# ipmi.net
KiCad netlist of a schematic drawn in Altium Designer
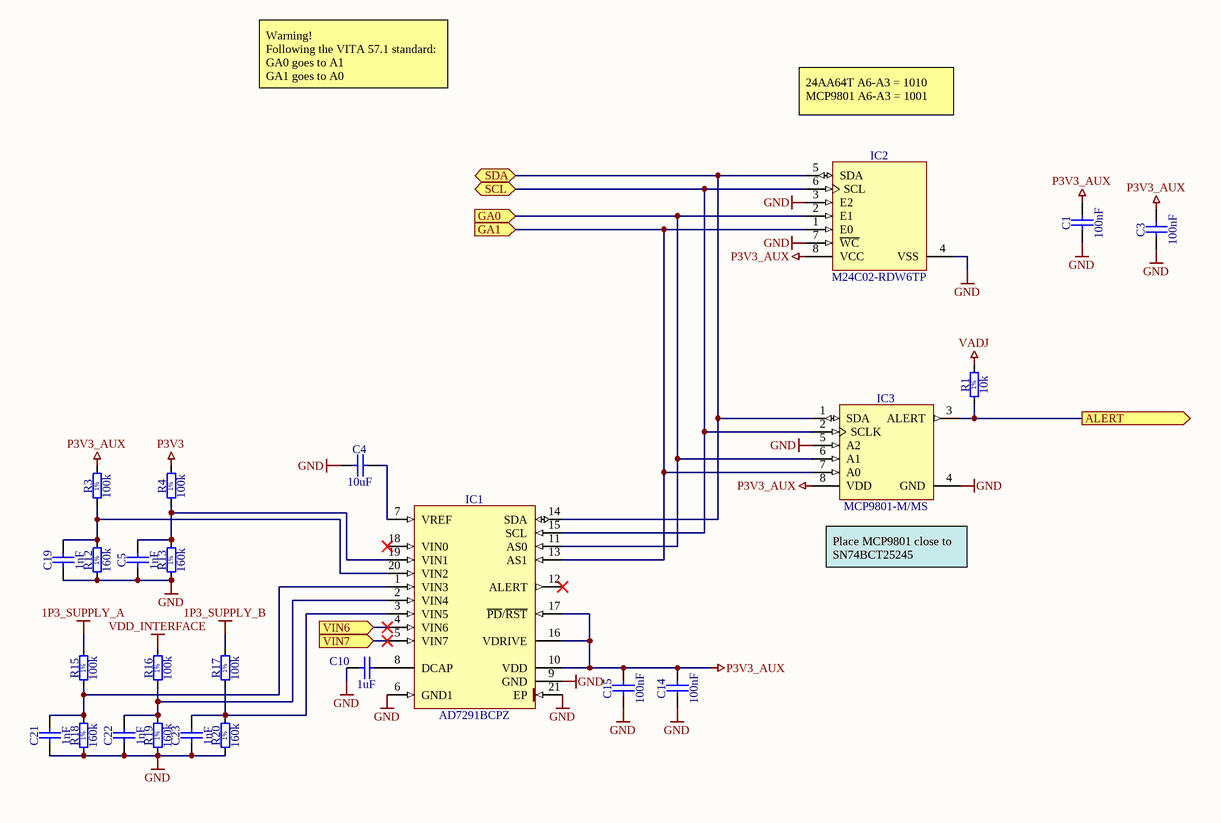
[diagram p0: ipmi.SchDoc]

(export (version "E")
  (design (tool "Eeschema 10.0.6"))
  (components
    (comp (ref "C1")
      (value "100nF")
      (footprint "CAPC1005X55N")
      (description "Non-polarised capacitor")
      (fields
        (field (name "PART NUMBER") "CC0402_100NF_16V_10%_X7R")
        (field (name "VOLTAGE") "16V")
        (field (name "AUTHOR") "CERN DEM JLC")
      )
      (libsource (lib "Capacitors") (part "Capacitor - non polarized"))
    )
    (comp (ref "C3")
      (value "100nF")
      (footprint "CAPC1005X55N")
      (description "Non-polarised capacitor")
      (fields
        (field (name "PART NUMBER") "CC0402_100NF_16V_10%_X7R")
        (field (name "VOLTAGE") "16V")
        (field (name "AUTHOR") "CERN DEM JLC")
      )
      (libsource (lib "Capacitors") (part "Capacitor - non polarized"))
    )
    (comp (ref "C4")
      (value "10uF")
      (footprint "CAPC1608X87N")
      (description "Non-polarised capacitor")
      (fields
        (field (name "PART NUMBER") "CC0603_10UF_6.3V_20%_X5R")
        (field (name "VOLTAGE") "6.3V")
        (field (name "AUTHOR") "CERN DEM JLC")
      )
      (libsource (lib "Capacitors") (part "Capacitor - non polarized"))
    )
    (comp (ref "C5")
      (value "1nF")
      (footprint "CAPC1005X55N")
      (description "Non-polarised capacitor")
      (fields
        (field (name "PART NUMBER") "CC0402_1NF_50V_10%_X7R")
        (field (name "VOLTAGE") "50V")
        (field (name "AUTHOR") "CERN DEM JLC")
      )
      (libsource (lib "Capacitors") (part "Capacitor - non polarized"))
    )
    (comp (ref "C10")
      (value "1uF")
      (footprint "CAPC1608X87N")
      (description "Non-polarised capacitor")
      (fields
        (field (name "PART NUMBER") "CC0603_1UF_16V_10%_X7R")
        (field (name "VOLTAGE") "16V")
        (field (name "AUTHOR") "CERN DEM JLC")
      )
      (libsource (lib "Capacitors") (part "Capacitor - non polarized"))
    )
    (comp (ref "C14")
      (value "100nF")
      (footprint "CAPC1005X55N")
      (description "Non-polarised capacitor")
      (fields
        (field (name "PART NUMBER") "CC0402_100NF_16V_10%_X7R")
        (field (name "VOLTAGE") "16V")
        (field (name "AUTHOR") "CERN DEM JLC")
      )
      (libsource (lib "Capacitors") (part "Capacitor - non polarized"))
    )
    (comp (ref "C15")
      (value "100nF")
      (footprint "CAPC1005X55N")
      (description "Non-polarised capacitor")
      (fields
        (field (name "PART NUMBER") "CC0402_100NF_16V_10%_X7R")
        (field (name "VOLTAGE") "16V")
        (field (name "AUTHOR") "CERN DEM JLC")
      )
      (libsource (lib "Capacitors") (part "Capacitor - non polarized"))
    )
    (comp (ref "C19")
      (value "1nF")
      (footprint "CAPC1005X55N")
      (description "Non-polarised capacitor")
      (fields
        (field (name "PART NUMBER") "CC0402_1NF_50V_10%_X7R")
        (field (name "VOLTAGE") "50V")
        (field (name "AUTHOR") "CERN DEM JLC")
      )
      (libsource (lib "Capacitors") (part "Capacitor - non polarized"))
    )
    (comp (ref "C21")
      (value "1nF")
      (footprint "CAPC1005X55N")
      (description "Non-polarised capacitor")
      (fields
        (field (name "PART NUMBER") "CC0402_1NF_50V_10%_X7R")
        (field (name "VOLTAGE") "50V")
        (field (name "AUTHOR") "CERN DEM JLC")
      )
      (libsource (lib "Capacitors") (part "Capacitor - non polarized"))
    )
    (comp (ref "C22")
      (value "1nF")
      (footprint "CAPC1005X55N")
      (description "Non-polarised capacitor")
      (fields
        (field (name "PART NUMBER") "CC0402_1NF_50V_10%_X7R")
        (field (name "VOLTAGE") "50V")
        (field (name "AUTHOR") "CERN DEM JLC")
      )
      (libsource (lib "Capacitors") (part "Capacitor - non polarized"))
    )
    (comp (ref "C23")
      (value "1nF")
      (footprint "CAPC1005X55N")
      (description "Non-polarised capacitor")
      (fields
        (field (name "PART NUMBER") "CC0402_1NF_50V_10%_X7R")
        (field (name "VOLTAGE") "50V")
        (field (name "AUTHOR") "CERN DEM JLC")
      )
      (libsource (lib "Capacitors") (part "Capacitor - non polarized"))
    )
    (comp (ref "IC1")
      (value "AD7291BCPZ")
      (footprint "QFN50P400X400X80-21N-S275")
      (description "8-Channel, I2C, 12-Bit SAR ADC with Temperature Sensor")
      (fields (field (name "MANUFACTURER") "ANALOG DEVICES") (field (name "AUTHOR") "CERN DEM JLC"))
      (libsource (lib "ICs And Semiconductors") (part "AD7291"))
    )
    (comp (ref "IC2")
      (value "M24C02-RDW6TP")
      (footprint "SOP65P640X120-8N")
      (description "2-Kbit (256 x 8bit) Serial I2C Bus EEPROM")
      (fields (field (name "MANUFACTURER") "ST MICROELECTRONICS") (field (name "AUTHOR") "CERN DEM JLC"))
      (libsource (lib "ICs And Semiconductors") (part "M24C02‐RDW"))
    )
    (comp (ref "IC3")
      (value "MCP9801-M/MS")
      (footprint "SOP65P490X110-8N")
      (description "2-Wire High-Accuracy Temperature Sensor")
      (fields (field (name "MANUFACTURER") "MICROCHIP TECHNOLOGIY") (field (name "AUTHOR") "CERN DEM JLC"))
      (libsource (lib "ICs And Semiconductors") (part "MCP9801-M/MS"))
    )
    (comp (ref "R1")
      (value "10k")
      (footprint "RESC1005X40N")
      (description "Resistor - 1%")
      (fields
        (field (name "PART NUMBER") "R0402_10K_1%_0.0625W_100PPM")
        (field (name "POWER") "0.0625W")
        (field (name "AUTHOR") "CERN DEM JLC")
      )
      (libsource (lib "Resistors") (part "Resistor - 1%"))
    )
    (comp (ref "R3")
      (value "100k")
      (footprint "RESC1005X40N")
      (description "Resistor - 1%")
      (fields
        (field (name "PART NUMBER") "R0402_100K_1%_0.0625W_100PPM")
        (field (name "POWER") "0.0625W")
        (field (name "AUTHOR") "CERN DEM JLC")
      )
      (libsource (lib "Resistors") (part "Resistor - 1%"))
    )
    (comp (ref "R4")
      (value "100k")
      (footprint "RESC1005X40N")
      (description "Resistor - 1%")
      (fields
        (field (name "PART NUMBER") "R0402_100K_1%_0.0625W_100PPM")
        (field (name "POWER") "0.0625W")
        (field (name "AUTHOR") "CERN DEM JLC")
      )
      (libsource (lib "Resistors") (part "Resistor - 1%"))
    )
    (comp (ref "R12")
      (value "160k")
      (footprint "RESC1005X40N")
      (description "Resistor - 1%")
      (fields
        (field (name "PART NUMBER") "R0402_160K_1%_0.0625W_100PPM")
        (field (name "POWER") "0.0625W")
        (field (name "AUTHOR") "CERN DEM JLC")
      )
      (libsource (lib "Resistors") (part "Resistor - 1%"))
    )
    (comp (ref "R13")
      (value "160k")
      (footprint "RESC1005X40N")
      (description "Resistor - 1%")
      (fields
        (field (name "PART NUMBER") "R0402_160K_1%_0.0625W_100PPM")
        (field (name "POWER") "0.0625W")
        (field (name "AUTHOR") "CERN DEM JLC")
      )
      (libsource (lib "Resistors") (part "Resistor - 1%"))
    )
    (comp (ref "R15")
      (value "100k")
      (footprint "RESC1005X40N")
      (description "Resistor - 1%")
      (fields
        (field (name "PART NUMBER") "R0402_100K_1%_0.0625W_100PPM")
        (field (name "POWER") "0.0625W")
        (field (name "AUTHOR") "CERN DEM JLC")
      )
      (libsource (lib "Resistors") (part "Resistor - 1%"))
    )
    (comp (ref "R16")
      (value "100k")
      (footprint "RESC1005X40N")
      (description "Resistor - 1%")
      (fields
        (field (name "PART NUMBER") "R0402_100K_1%_0.0625W_100PPM")
        (field (name "POWER") "0.0625W")
        (field (name "AUTHOR") "CERN DEM JLC")
      )
      (libsource (lib "Resistors") (part "Resistor - 1%"))
    )
    (comp (ref "R17")
      (value "100k")
      (footprint "RESC1005X40N")
      (description "Resistor - 1%")
      (fields
        (field (name "PART NUMBER") "R0402_100K_1%_0.0625W_100PPM")
        (field (name "POWER") "0.0625W")
        (field (name "AUTHOR") "CERN DEM JLC")
      )
      (libsource (lib "Resistors") (part "Resistor - 1%"))
    )
    (comp (ref "R18")
      (value "160k")
      (footprint "RESC1005X40N")
      (description "Resistor - 1%")
      (fields
        (field (name "PART NUMBER") "R0402_160K_1%_0.0625W_100PPM")
        (field (name "POWER") "0.0625W")
        (field (name "AUTHOR") "CERN DEM JLC")
      )
      (libsource (lib "Resistors") (part "Resistor - 1%"))
    )
    (comp (ref "R19")
      (value "160k")
      (footprint "RESC1005X40N")
      (description "Resistor - 1%")
      (fields
        (field (name "PART NUMBER") "R0402_160K_1%_0.0625W_100PPM")
        (field (name "POWER") "0.0625W")
        (field (name "AUTHOR") "CERN DEM JLC")
      )
      (libsource (lib "Resistors") (part "Resistor - 1%"))
    )
    (comp (ref "R20")
      (value "160k")
      (footprint "RESC1005X40N")
      (description "Resistor - 1%")
      (fields
        (field (name "PART NUMBER") "R0402_160K_1%_0.0625W_100PPM")
        (field (name "POWER") "0.0625W")
        (field (name "AUTHOR") "CERN DEM JLC")
      )
      (libsource (lib "Resistors") (part "Resistor - 1%"))
    )
  )
  (nets
    (net (code "1") (name "/ALERT") (class "Default")
      (node (ref "IC3") (pin "3") (pinfunction "ALERT_3") (pintype "output"))
      (node (ref "R1") (pin "1") (pinfunction "1_1") (pintype "passive"))
    )
    (net (code "2") (name "/GA0") (class "Default")
      (node (ref "IC1") (pin "11") (pinfunction "AS0_11") (pintype "input"))
      (node (ref "IC2") (pin "2") (pinfunction "E1_2") (pintype "input"))
      (node (ref "IC3") (pin "6") (pinfunction "A1_6") (pintype "input"))
    )
    (net (code "3") (name "/GA1") (class "Default")
      (node (ref "IC1") (pin "13") (pinfunction "AS1_13") (pintype "input"))
      (node (ref "IC2") (pin "1") (pinfunction "E0_1") (pintype "input"))
      (node (ref "IC3") (pin "7") (pinfunction "A0_7") (pintype "input"))
    )
    (net (code "4") (name "/SCL") (class "Default")
      (node (ref "IC1") (pin "15") (pinfunction "SCL_15") (pintype "input"))
      (node (ref "IC2") (pin "6") (pinfunction "SCL_6") (pintype "input"))
      (node (ref "IC3") (pin "2") (pinfunction "SCLK_2") (pintype "input"))
    )
    (net (code "5") (name "/SDA") (class "Default")
      (node (ref "IC1") (pin "14") (pinfunction "SDA_14") (pintype "bidirectional"))
      (node (ref "IC2") (pin "5") (pinfunction "SDA_5") (pintype "bidirectional"))
      (node (ref "IC3") (pin "1") (pinfunction "SDA_1") (pintype "bidirectional"))
    )
    (net (code "6") (name "/VIN6") (class "Default")
      (node (ref "IC1") (pin "4") (pinfunction "VIN6_4") (pintype "input+no_connect"))
    )
    (net (code "7") (name "/VIN7") (class "Default")
      (node (ref "IC1") (pin "5") (pinfunction "VIN7_5") (pintype "input+no_connect"))
    )
    (net (code "8") (name "1P3_SUPPLY_A") (class "Default")
      (node (ref "R15") (pin "2") (pinfunction "2_2") (pintype "passive"))
    )
    (net (code "9") (name "1P3_SUPPLY_B") (class "Default")
      (node (ref "R17") (pin "2") (pinfunction "2_2") (pintype "passive"))
    )
    (net (code "10") (name "GND") (class "Default")
      (node (ref "C1") (pin "1") (pinfunction "1_1") (pintype "passive"))
      (node (ref "C10") (pin "1") (pinfunction "1_1") (pintype "passive"))
      (node (ref "C14") (pin "1") (pinfunction "1_1") (pintype "passive"))
      (node (ref "C15") (pin "1") (pinfunction "1_1") (pintype "passive"))
      (node (ref "C19") (pin "1") (pinfunction "1_1") (pintype "passive"))
      (node (ref "C21") (pin "1") (pinfunction "1_1") (pintype "passive"))
      (node (ref "C22") (pin "1") (pinfunction "1_1") (pintype "passive"))
      (node (ref "C23") (pin "1") (pinfunction "1_1") (pintype "passive"))
      (node (ref "C3") (pin "1") (pinfunction "1_1") (pintype "passive"))
      (node (ref "C4") (pin "1") (pinfunction "1_1") (pintype "passive"))
      (node (ref "C5") (pin "1") (pinfunction "1_1") (pintype "passive"))
      (node (ref "IC1") (pin "21") (pinfunction "EP_21") (pintype "input"))
      (node (ref "IC1") (pin "6") (pinfunction "GND1_6") (pintype "input"))
      (node (ref "IC1") (pin "9") (pinfunction "GND_9") (pintype "power_in"))
      (node (ref "IC2") (pin "3") (pinfunction "E2_3") (pintype "input"))
      (node (ref "IC2") (pin "4") (pinfunction "VSS_4") (pintype "power_in"))
      (node (ref "IC2") (pin "7") (pinfunction "~{WC}_7") (pintype "input"))
      (node (ref "IC3") (pin "4") (pinfunction "GND_4") (pintype "power_in"))
      (node (ref "IC3") (pin "5") (pinfunction "A2_5") (pintype "input"))
      (node (ref "R12") (pin "1") (pinfunction "1_1") (pintype "passive"))
      (node (ref "R13") (pin "1") (pinfunction "1_1") (pintype "passive"))
      (node (ref "R18") (pin "1") (pinfunction "1_1") (pintype "passive"))
      (node (ref "R19") (pin "1") (pinfunction "1_1") (pintype "passive"))
      (node (ref "R20") (pin "1") (pinfunction "1_1") (pintype "passive"))
    )
    (net (code "11") (name "Net-(IC1-DCAP)") (class "Default")
      (node (ref "C10") (pin "2") (pinfunction "2_2") (pintype "passive"))
      (node (ref "IC1") (pin "8") (pinfunction "DCAP_8") (pintype "passive"))
    )
    (net (code "12") (name "Net-(IC1-VIN1)") (class "Default")
      (node (ref "C5") (pin "2") (pinfunction "2_2") (pintype "passive"))
      (node (ref "IC1") (pin "19") (pinfunction "VIN1_19") (pintype "input"))
      (node (ref "R13") (pin "2") (pinfunction "2_2") (pintype "passive"))
      (node (ref "R4") (pin "1") (pinfunction "1_1") (pintype "passive"))
    )
    (net (code "13") (name "Net-(IC1-VIN2)") (class "Default")
      (node (ref "C19") (pin "2") (pinfunction "2_2") (pintype "passive"))
      (node (ref "IC1") (pin "20") (pinfunction "VIN2_20") (pintype "input"))
      (node (ref "R12") (pin "2") (pinfunction "2_2") (pintype "passive"))
      (node (ref "R3") (pin "1") (pinfunction "1_1") (pintype "passive"))
    )
    (net (code "14") (name "Net-(IC1-VIN3)") (class "Default")
      (node (ref "C21") (pin "2") (pinfunction "2_2") (pintype "passive"))
      (node (ref "IC1") (pin "1") (pinfunction "VIN3_1") (pintype "input"))
      (node (ref "R15") (pin "1") (pinfunction "1_1") (pintype "passive"))
      (node (ref "R18") (pin "2") (pinfunction "2_2") (pintype "passive"))
    )
    (net (code "15") (name "Net-(IC1-VIN4)") (class "Default")
      (node (ref "C22") (pin "2") (pinfunction "2_2") (pintype "passive"))
      (node (ref "IC1") (pin "2") (pinfunction "VIN4_2") (pintype "input"))
      (node (ref "R16") (pin "1") (pinfunction "1_1") (pintype "passive"))
      (node (ref "R19") (pin "2") (pinfunction "2_2") (pintype "passive"))
    )
    (net (code "16") (name "Net-(IC1-VIN5)") (class "Default")
      (node (ref "C23") (pin "2") (pinfunction "2_2") (pintype "passive"))
      (node (ref "IC1") (pin "3") (pinfunction "VIN5_3") (pintype "input"))
      (node (ref "R17") (pin "1") (pinfunction "1_1") (pintype "passive"))
      (node (ref "R20") (pin "2") (pinfunction "2_2") (pintype "passive"))
    )
    (net (code "17") (name "Net-(IC1-VREF)") (class "Default")
      (node (ref "C4") (pin "2") (pinfunction "2_2") (pintype "passive"))
      (node (ref "IC1") (pin "7") (pinfunction "VREF_7") (pintype "input"))
    )
    (net (code "18") (name "P3V3") (class "Default")
      (node (ref "R4") (pin "2") (pinfunction "2_2") (pintype "passive"))
    )
    (net (code "19") (name "P3V3_AUX") (class "Default")
      (node (ref "C1") (pin "2") (pinfunction "2_2") (pintype "passive"))
      (node (ref "C14") (pin "2") (pinfunction "2_2") (pintype "passive"))
      (node (ref "C15") (pin "2") (pinfunction "2_2") (pintype "passive"))
      (node (ref "C3") (pin "2") (pinfunction "2_2") (pintype "passive"))
      (node (ref "IC1") (pin "10") (pinfunction "VDD_10") (pintype "power_in"))
      (node (ref "IC1") (pin "16") (pinfunction "VDRIVE_16") (pintype "power_in"))
      (node (ref "IC1") (pin "17") (pinfunction "~{PD}/~{RST}_17") (pintype "input"))
      (node (ref "IC2") (pin "8") (pinfunction "VCC_8") (pintype "power_in"))
      (node (ref "IC3") (pin "8") (pinfunction "VDD_8") (pintype "power_in"))
      (node (ref "R3") (pin "2") (pinfunction "2_2") (pintype "passive"))
    )
    (net (code "20") (name "VADJ") (class "Default")
      (node (ref "R1") (pin "2") (pinfunction "2_2") (pintype "passive"))
    )
    (net (code "21") (name "VDD_INTERFACE") (class "Default")
      (node (ref "R16") (pin "2") (pinfunction "2_2") (pintype "passive"))
    )
    (net (code "22") (name "unconnected-(IC1-ALERT-Pad12)") (class "Default")
      (node (ref "IC1") (pin "12") (pinfunction "ALERT_12") (pintype "output+no_connect"))
    )
    (net (code "23") (name "unconnected-(IC1-VIN0-Pad18)") (class "Default")
      (node (ref "IC1") (pin "18") (pinfunction "VIN0_18") (pintype "input+no_connect"))
    )
  )
)
